# BT111_v1.net
KiCad netlist of a schematic drawn in EAGLE
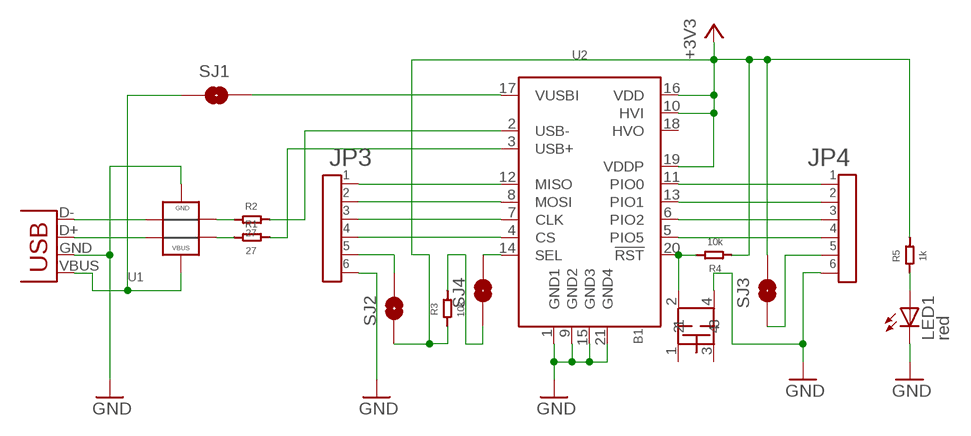
[diagram p0: schematic, sheet 1]

(export (version "E")
  (design (tool "Eeschema 10.0.6"))
  (components
    (comp (ref "B1")
      (value "BUTTON_ALPS_5.2MM_SMD")
      (footprint "eagle-import:BUTTON_ALPS_SMD_5.2MM_SKQG")
      (libsource (lib "eagle-import") (part "BUTTON_ALPS_5.2MM_SMD"))
    )
    (comp (ref "JP1")
      (value "USB-A-H")
      (footprint "eagle-import:USB-A-H")
      (libsource (lib "eagle-import") (part "USB-A-H"))
    )
    (comp (ref "JP3")
      (value "PIN1X6PTH_SMALL")
      (footprint "eagle-import:PIN_1X6_S")
      (libsource (lib "eagle-import") (part "PIN1X6PTH_SMALL"))
    )
    (comp (ref "JP4")
      (value "PIN1X6PTH_SMALL")
      (footprint "eagle-import:PIN_1X6_S")
      (libsource (lib "eagle-import") (part "PIN1X6PTH_SMALL"))
    )
    (comp (ref "LED1")
      (value "red")
      (footprint "eagle-import:CHIP-LED0805")
      (libsource (lib "eagle-import") (part "LEDCHIP-LED0805"))
    )
    (comp (ref "R1")
      (value "27")
      (footprint "eagle-import:0603")
      (libsource (lib "eagle-import") (part "RESISTOR0603"))
    )
    (comp (ref "R2")
      (value "27")
      (footprint "eagle-import:0603")
      (libsource (lib "eagle-import") (part "RESISTOR0603"))
    )
    (comp (ref "R3")
      (value "10k")
      (footprint "eagle-import:0603")
      (libsource (lib "eagle-import") (part "RESISTOR0603"))
    )
    (comp (ref "R4")
      (value "10k")
      (footprint "eagle-import:0603")
      (libsource (lib "eagle-import") (part "RESISTOR0603"))
    )
    (comp (ref "R5")
      (value "1k")
      (footprint "eagle-import:0603")
      (libsource (lib "eagle-import") (part "RESISTOR0603"))
    )
    (comp (ref "SJ1")
      (value "USBPOW")
      (footprint "eagle-import:SJ_2S")
      (libsource (lib "eagle-import") (part "SOLDERJUMPERNC"))
    )
    (comp (ref "SJ2")
      (value "SPIPOW")
      (footprint "eagle-import:SJ_2S-NO")
      (libsource (lib "eagle-import") (part "SOLDERJUMPERNO"))
    )
    (comp (ref "SJ3")
      (value "PIOPOW")
      (footprint "eagle-import:SJ_2S-NO")
      (libsource (lib "eagle-import") (part "SOLDERJUMPERNO"))
    )
    (comp (ref "SJ4")
      (value "PCMSEL")
      (footprint "eagle-import:SJ_2S-NO")
      (libsource (lib "eagle-import") (part "SOLDERJUMPERNO"))
    )
    (comp (ref "U1")
      (value "ST_USBLC6-2")
      (footprint "eagle-import:SOT-23-6L")
      (libsource (lib "eagle-import") (part "ST_USBLC6-2"))
    )
    (comp (ref "U2")
      (value "BT111")
      (footprint "eagle-import:BT111")
      (libsource (lib "eagle-import") (part "BT111"))
    )
  )
  (nets
    (net (code "1") (name "+3V3") (class "Default")
      (node (ref "R3") (pin "1") (pinfunction "1_1") (pintype "passive"))
      (node (ref "R4") (pin "1") (pinfunction "1_1") (pintype "passive"))
      (node (ref "R5") (pin "2") (pinfunction "2_2") (pintype "passive"))
      (node (ref "SJ2") (pin "1") (pinfunction "1_1") (pintype "passive"))
      (node (ref "SJ3") (pin "2") (pinfunction "2_2") (pintype "passive"))
      (node (ref "U2") (pin "10") (pinfunction "HVI_10") (pintype "bidirectional"))
      (node (ref "U2") (pin "16") (pinfunction "VDD_16") (pintype "bidirectional"))
      (node (ref "U2") (pin "19") (pinfunction "VDDP_19") (pintype "bidirectional"))
    )
    (net (code "2") (name "GND") (class "Default")
      (node (ref "B1") (pin "4") (pinfunction "4_4") (pintype "bidirectional"))
      (node (ref "JP1") (pin "GND") (pinfunction "VBUS_GND") (pintype "bidirectional"))
      (node (ref "JP3") (pin "6") (pinfunction "6_6") (pintype "bidirectional"))
      (node (ref "JP4") (pin "6") (pinfunction "6_6") (pintype "bidirectional"))
      (node (ref "LED1") (pin "C") (pinfunction "C_C") (pintype "passive"))
      (node (ref "U1") (pin "2") (pinfunction "GND_2") (pintype "bidirectional"))
      (node (ref "U2") (pin "1") (pinfunction "GND1_1") (pintype "bidirectional"))
      (node (ref "U2") (pin "15") (pinfunction "GND3_15") (pintype "bidirectional"))
      (node (ref "U2") (pin "21") (pinfunction "GND4_21") (pintype "bidirectional"))
      (node (ref "U2") (pin "9") (pinfunction "GND2_9") (pintype "bidirectional"))
    )
    (net (code "3") (name "Net-(JP1-D+)") (class "Default")
      (node (ref "JP1") (pin "D-") (pinfunction "D+_D-") (pintype "bidirectional"))
      (node (ref "U1") (pin "3") (pinfunction "IO2A_3") (pintype "bidirectional"))
    )
    (net (code "4") (name "Net-(JP1-D-)") (class "Default")
      (node (ref "JP1") (pin "D+") (pinfunction "D-_D+") (pintype "bidirectional"))
      (node (ref "U1") (pin "1") (pinfunction "IO1A_1") (pintype "bidirectional"))
    )
    (net (code "5") (name "Net-(JP1-GND)") (class "Default")
      (node (ref "JP1") (pin "VBUS") (pinfunction "GND_VBUS") (pintype "bidirectional"))
      (node (ref "SJ1") (pin "1") (pinfunction "1_1") (pintype "passive"))
      (node (ref "U1") (pin "5") (pinfunction "VBUS_5") (pintype "bidirectional"))
    )
    (net (code "6") (name "Net-(JP3-Pad5)") (class "Default")
      (node (ref "JP3") (pin "5") (pinfunction "5_5") (pintype "bidirectional"))
      (node (ref "SJ2") (pin "2") (pinfunction "2_2") (pintype "passive"))
    )
    (net (code "7") (name "Net-(JP4-Pad5)") (class "Default")
      (node (ref "JP4") (pin "5") (pinfunction "5_5") (pintype "bidirectional"))
      (node (ref "SJ3") (pin "1") (pinfunction "1_1") (pintype "passive"))
    )
    (net (code "8") (name "Net-(LED1-PadA)") (class "Default")
      (node (ref "LED1") (pin "A") (pinfunction "A_A") (pintype "passive"))
      (node (ref "R5") (pin "1") (pinfunction "1_1") (pintype "passive"))
    )
    (net (code "9") (name "Net-(R3-Pad2)") (class "Default")
      (node (ref "R3") (pin "2") (pinfunction "2_2") (pintype "passive"))
      (node (ref "SJ4") (pin "1") (pinfunction "1_1") (pintype "passive"))
    )
    (net (code "10") (name "Net-(U1-IO1B)") (class "Default")
      (node (ref "R1") (pin "1") (pinfunction "1_1") (pintype "passive"))
      (node (ref "U1") (pin "6") (pinfunction "IO1B_6") (pintype "bidirectional"))
    )
    (net (code "11") (name "Net-(U1-IO2B)") (class "Default")
      (node (ref "R2") (pin "1") (pinfunction "1_1") (pintype "passive"))
      (node (ref "U1") (pin "4") (pinfunction "IO2B_4") (pintype "bidirectional"))
    )
    (net (code "12") (name "Net-(U2-CLK)") (class "Default")
      (node (ref "JP3") (pin "3") (pinfunction "3_3") (pintype "bidirectional"))
      (node (ref "U2") (pin "7") (pinfunction "CLK_7") (pintype "bidirectional"))
    )
    (net (code "13") (name "Net-(U2-CS)") (class "Default")
      (node (ref "JP3") (pin "4") (pinfunction "4_4") (pintype "bidirectional"))
      (node (ref "U2") (pin "4") (pinfunction "CS_4") (pintype "bidirectional"))
    )
    (net (code "14") (name "Net-(U2-MISO)") (class "Default")
      (node (ref "JP3") (pin "1") (pinfunction "1_1") (pintype "bidirectional"))
      (node (ref "U2") (pin "12") (pinfunction "MISO_12") (pintype "bidirectional"))
    )
    (net (code "15") (name "Net-(U2-MOSI)") (class "Default")
      (node (ref "JP3") (pin "2") (pinfunction "2_2") (pintype "bidirectional"))
      (node (ref "U2") (pin "8") (pinfunction "MOSI_8") (pintype "bidirectional"))
    )
    (net (code "16") (name "Net-(U2-PIO0)") (class "Default")
      (node (ref "JP4") (pin "1") (pinfunction "1_1") (pintype "bidirectional"))
      (node (ref "U2") (pin "11") (pinfunction "PIO0_11") (pintype "bidirectional"))
    )
    (net (code "17") (name "Net-(U2-PIO1)") (class "Default")
      (node (ref "JP4") (pin "2") (pinfunction "2_2") (pintype "bidirectional"))
      (node (ref "U2") (pin "13") (pinfunction "PIO1_13") (pintype "bidirectional"))
    )
    (net (code "18") (name "Net-(U2-PIO2)") (class "Default")
      (node (ref "JP4") (pin "3") (pinfunction "3_3") (pintype "bidirectional"))
      (node (ref "U2") (pin "6") (pinfunction "PIO2_6") (pintype "bidirectional"))
    )
    (net (code "19") (name "Net-(U2-PIO5)") (class "Default")
      (node (ref "JP4") (pin "4") (pinfunction "4_4") (pintype "bidirectional"))
      (node (ref "U2") (pin "5") (pinfunction "PIO5_5") (pintype "bidirectional"))
    )
    (net (code "20") (name "Net-(U2-SEL)") (class "Default")
      (node (ref "SJ4") (pin "2") (pinfunction "2_2") (pintype "passive"))
      (node (ref "U2") (pin "14") (pinfunction "SEL_14") (pintype "bidirectional"))
    )
    (net (code "21") (name "Net-(U2-USB+)") (class "Default")
      (node (ref "R1") (pin "2") (pinfunction "2_2") (pintype "passive"))
      (node (ref "U2") (pin "3") (pinfunction "USB+_3") (pintype "bidirectional"))
    )
    (net (code "22") (name "Net-(U2-USB-)") (class "Default")
      (node (ref "R2") (pin "2") (pinfunction "2_2") (pintype "passive"))
      (node (ref "U2") (pin "2") (pinfunction "USB-_2") (pintype "bidirectional"))
    )
    (net (code "23") (name "Net-(U2-VUSBI)") (class "Default")
      (node (ref "SJ1") (pin "2") (pinfunction "2_2") (pintype "passive"))
      (node (ref "U2") (pin "17") (pinfunction "VUSBI_17") (pintype "bidirectional"))
    )
    (net (code "24") (name "Net-(U2-~{RST})") (class "Default")
      (node (ref "B1") (pin "2") (pinfunction "2_2") (pintype "bidirectional"))
      (node (ref "R4") (pin "2") (pinfunction "2_2") (pintype "passive"))
      (node (ref "U2") (pin "20") (pinfunction "~{RST}_20") (pintype "bidirectional"))
    )
    (net (code "25") (name "unconnected-(B1-Pad1)") (class "Default")
      (node (ref "B1") (pin "1") (pinfunction "1_1") (pintype "bidirectional"))
    )
    (net (code "26") (name "unconnected-(B1-Pad3)") (class "Default")
      (node (ref "B1") (pin "3") (pinfunction "3_3") (pintype "bidirectional"))
    )
    (net (code "27") (name "unconnected-(U2-HVO-Pad18)") (class "Default")
      (node (ref "U2") (pin "18") (pinfunction "HVO_18") (pintype "bidirectional"))
    )
  )
)
